# Power_Module_3_0.net
KiCad netlist of a schematic drawn in EAGLE
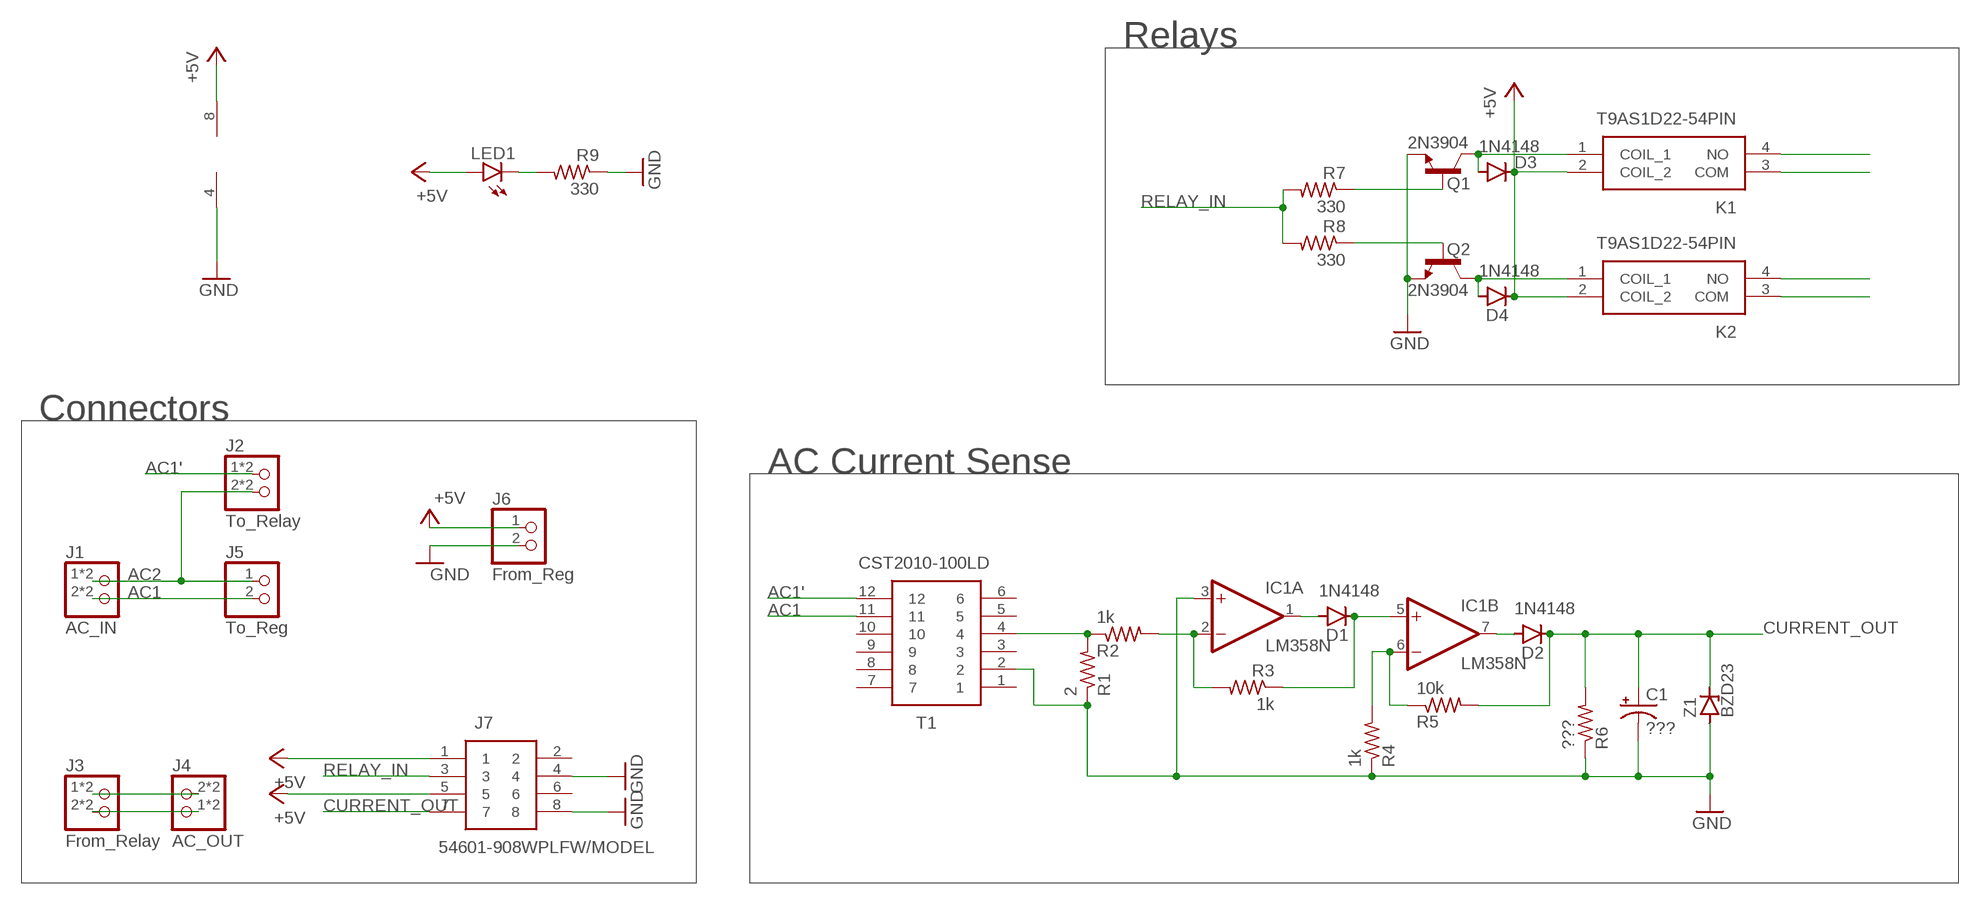
[diagram p0: schematic, sheet 1]

(export (version "E")
  (design (tool "Eeschema 10.0.6"))
  (components
    (comp (ref "C1")
      (value "???")
      (footprint "eagle-import:E1,8-4")
      (libsource (lib "eagle-import") (part "CPOL-USE1.8-4"))
    )
    (comp (ref "D1")
      (value "1N4148")
      (footprint "eagle-import:DO35-7")
      (libsource (lib "eagle-import") (part "1N4148DO35-7"))
    )
    (comp (ref "D2")
      (value "1N4148")
      (footprint "eagle-import:DO35-7")
      (libsource (lib "eagle-import") (part "1N4148DO35-7"))
    )
    (comp (ref "D3")
      (value "1N4148")
      (footprint "eagle-import:DO35-7")
      (libsource (lib "eagle-import") (part "1N4148DO35-7"))
    )
    (comp (ref "D4")
      (value "1N4148")
      (footprint "eagle-import:DO35-7")
      (libsource (lib "eagle-import") (part "1N4148DO35-7"))
    )
    (comp (ref "IC1")
      (value "LM358N")
      (footprint "eagle-import:DIL08")
      (libsource (lib "eagle-import") (part "LM358N"))
    )
    (comp (ref "J1")
      (value "AC_IN")
      (footprint "eagle-import:HDRRA4W64P762_2X2_1016X254X556B")
      (libsource (lib "eagle-import") (part "VC0200500000GVC0200500000G"))
    )
    (comp (ref "J2")
      (value "To_Relay")
      (footprint "eagle-import:HDRRA4W64P762_2X2_1016X254X556B")
      (libsource (lib "eagle-import") (part "VC0200500000GVC0200500000G"))
    )
    (comp (ref "J3")
      (value "From_Relay")
      (footprint "eagle-import:HDRRA4W64P762_2X2_1016X254X556B")
      (libsource (lib "eagle-import") (part "VC0200500000GVC0200500000G"))
    )
    (comp (ref "J4")
      (value "AC_OUT")
      (footprint "eagle-import:HDRRA4W64P762_2X2_1016X254X556B")
      (libsource (lib "eagle-import") (part "VC0200500000GVC0200500000G"))
    )
    (comp (ref "J5")
      (value "To_Reg")
      (footprint "eagle-import:HDRV2W64P792_1X2_1016X508X838B")
      (libsource (lib "eagle-import") (part "VH_1X2GAP"))
    )
    (comp (ref "J6")
      (value "From_Reg")
      (footprint "eagle-import:HDRV2W165P396_1X2_1016X508X838B")
      (libsource (lib "eagle-import") (part "VH_1X2"))
    )
    (comp (ref "J7")
      (value "54601-908WPLFW/MODEL")
      (footprint "eagle-import:HDRV4W64P254_1X4_1016X508X838B")
      (libsource (lib "eagle-import") (part "54601-908WPLFW/MODEL"))
    )
    (comp (ref "K1")
      (value "T9AS1D22-54PIN")
      (footprint "eagle-import:T9AS5D1212313932103-2")
      (libsource (lib "eagle-import") (part "T9AS1D22-54PIN"))
    )
    (comp (ref "K2")
      (value "T9AS1D22-54PIN")
      (footprint "eagle-import:T9AS5D1212313932103-2")
      (libsource (lib "eagle-import") (part "T9AS1D22-54PIN"))
    )
    (comp (ref "LED1")
      (value "LED5MM")
      (footprint "eagle-import:LED5MM")
      (libsource (lib "eagle-import") (part "LED5MM"))
    )
    (comp (ref "Q1")
      (value "2N3904")
      (footprint "eagle-import:TO92")
      (libsource (lib "eagle-import") (part "2N3904"))
    )
    (comp (ref "Q2")
      (value "2N3904")
      (footprint "eagle-import:TO92")
      (libsource (lib "eagle-import") (part "2N3904"))
    )
    (comp (ref "R1")
      (value "2")
      (footprint "eagle-import:0204_7")
      (libsource (lib "eagle-import") (part "R-US"))
    )
    (comp (ref "R2")
      (value "1k")
      (footprint "eagle-import:0204_7")
      (libsource (lib "eagle-import") (part "R-US"))
    )
    (comp (ref "R3")
      (value "1k")
      (footprint "eagle-import:0204_7")
      (libsource (lib "eagle-import") (part "R-US"))
    )
    (comp (ref "R4")
      (value "1k")
      (footprint "eagle-import:0204_7")
      (libsource (lib "eagle-import") (part "R-US"))
    )
    (comp (ref "R5")
      (value "10k")
      (footprint "eagle-import:0204_7")
      (libsource (lib "eagle-import") (part "R-US"))
    )
    (comp (ref "R6")
      (value "???")
      (footprint "eagle-import:0204_7")
      (libsource (lib "eagle-import") (part "R-US"))
    )
    (comp (ref "R7")
      (value "330")
      (footprint "eagle-import:0204_7")
      (libsource (lib "eagle-import") (part "R-US"))
    )
    (comp (ref "R8")
      (value "330")
      (footprint "eagle-import:0204_7")
      (libsource (lib "eagle-import") (part "R-US"))
    )
    (comp (ref "R9")
      (value "330")
      (footprint "eagle-import:0204_7")
      (libsource (lib "eagle-import") (part "R-US"))
    )
    (comp (ref "T1")
      (value "CST2010-100LD")
      (footprint "eagle-import:CST2010100LD")
      (fields (field (name "MOUSER_PART_NUMBER") "994-CST2010-100LD"))
      (libsource (lib "eagle-import") (part "CST2010-100LD"))
    )
    (comp (ref "Z1")
      (value "BZD23")
      (footprint "eagle-import:SOD81")
      (libsource (lib "eagle-import") (part "BZD23"))
    )
  )
  (nets
    (net (code "1") (name "+5V") (class "Default")
      (node (ref "D3") (pin "C") (pinfunction "C_C") (pintype "passive"))
      (node (ref "D4") (pin "C") (pinfunction "C_C") (pintype "passive"))
      (node (ref "IC1") (pin "8") (pinfunction "V+_8") (pintype "power_in"))
      (node (ref "J6") (pin "1") (pinfunction "1_1") (pintype "passive"))
      (node (ref "J7") (pin "1") (pinfunction "1_1") (pintype "bidirectional"))
      (node (ref "J7") (pin "5") (pinfunction "5_5") (pintype "bidirectional"))
      (node (ref "K1") (pin "2") (pinfunction "COIL_2_2") (pintype "bidirectional"))
      (node (ref "K2") (pin "2") (pinfunction "COIL_2_2") (pintype "bidirectional"))
      (node (ref "LED1") (pin "A") (pinfunction "A_A") (pintype "passive"))
    )
    (net (code "2") (name "/AC1") (class "Default")
      (node (ref "J1") (pin "2") (pinfunction "2_2") (pintype "passive"))
      (node (ref "J1") (pin "3") (pinfunction "2_3") (pintype "passive"))
      (node (ref "J5") (pin "2") (pinfunction "2_2") (pintype "passive"))
      (node (ref "T1") (pin "11") (pinfunction "11_11") (pintype "bidirectional"))
    )
    (net (code "3") (name "/AC1'") (class "Default")
      (node (ref "J2") (pin "1") (pinfunction "1_1") (pintype "passive"))
      (node (ref "J2") (pin "4") (pinfunction "1_4") (pintype "passive"))
      (node (ref "T1") (pin "12") (pinfunction "12_12") (pintype "bidirectional"))
    )
    (net (code "4") (name "/AC2") (class "Default")
      (node (ref "J1") (pin "1") (pinfunction "1_1") (pintype "passive"))
      (node (ref "J1") (pin "4") (pinfunction "1_4") (pintype "passive"))
      (node (ref "J2") (pin "2") (pinfunction "2_2") (pintype "passive"))
      (node (ref "J2") (pin "3") (pinfunction "2_3") (pintype "passive"))
      (node (ref "J5") (pin "1") (pinfunction "1_1") (pintype "passive"))
    )
    (net (code "5") (name "/CURRENT_OUT") (class "Default")
      (node (ref "C1") (pin "+") (pinfunction "+_+") (pintype "passive"))
      (node (ref "D2") (pin "C") (pinfunction "C_C") (pintype "passive"))
      (node (ref "J7") (pin "7") (pinfunction "7_7") (pintype "bidirectional"))
      (node (ref "R5") (pin "2") (pinfunction "2_2") (pintype "passive"))
      (node (ref "R6") (pin "2") (pinfunction "2_2") (pintype "passive"))
      (node (ref "Z1") (pin "C") (pinfunction "C_C") (pintype "passive"))
    )
    (net (code "6") (name "/RELAY_IN") (class "Default")
      (node (ref "J7") (pin "3") (pinfunction "3_3") (pintype "bidirectional"))
      (node (ref "R7") (pin "2") (pinfunction "2_2") (pintype "passive"))
      (node (ref "R8") (pin "2") (pinfunction "2_2") (pintype "passive"))
    )
    (net (code "7") (name "GND") (class "Default")
      (node (ref "C1") (pin "-") (pinfunction "-_-") (pintype "passive"))
      (node (ref "IC1") (pin "3") (pinfunction "+IN_3") (pintype "input"))
      (node (ref "IC1") (pin "4") (pinfunction "V-_4") (pintype "power_in"))
      (node (ref "J6") (pin "2") (pinfunction "2_2") (pintype "passive"))
      (node (ref "J7") (pin "4") (pinfunction "4_4") (pintype "bidirectional"))
      (node (ref "J7") (pin "8") (pinfunction "8_8") (pintype "bidirectional"))
      (node (ref "Q1") (pin "3") (pinfunction "E_3") (pintype "passive"))
      (node (ref "Q2") (pin "3") (pinfunction "E_3") (pintype "passive"))
      (node (ref "R1") (pin "1") (pinfunction "1_1") (pintype "passive"))
      (node (ref "R4") (pin "1") (pinfunction "1_1") (pintype "passive"))
      (node (ref "R6") (pin "1") (pinfunction "1_1") (pintype "passive"))
      (node (ref "R9") (pin "1") (pinfunction "1_1") (pintype "passive"))
      (node (ref "T1") (pin "2") (pinfunction "2_2") (pintype "bidirectional"))
      (node (ref "Z1") (pin "A") (pinfunction "A_A") (pintype "passive"))
    )
    (net (code "8") (name "Net-(IC1A--IN)") (class "Default")
      (node (ref "IC1") (pin "2") (pinfunction "-IN_2") (pintype "input"))
      (node (ref "R2") (pin "2") (pinfunction "2_2") (pintype "passive"))
      (node (ref "R3") (pin "2") (pinfunction "2_2") (pintype "passive"))
    )
    (net (code "9") (name "Net-(IC1A-OUT)") (class "Default")
      (node (ref "D1") (pin "A") (pinfunction "A_A") (pintype "passive"))
      (node (ref "IC1") (pin "1") (pinfunction "OUT_1") (pintype "output"))
    )
    (net (code "10") (name "Net-(IC1B-+IN)") (class "Default")
      (node (ref "D1") (pin "C") (pinfunction "C_C") (pintype "passive"))
      (node (ref "IC1") (pin "5") (pinfunction "+IN_5") (pintype "input"))
      (node (ref "R3") (pin "1") (pinfunction "1_1") (pintype "passive"))
    )
    (net (code "11") (name "Net-(IC1B--IN)") (class "Default")
      (node (ref "IC1") (pin "6") (pinfunction "-IN_6") (pintype "input"))
      (node (ref "R4") (pin "2") (pinfunction "2_2") (pintype "passive"))
      (node (ref "R5") (pin "1") (pinfunction "1_1") (pintype "passive"))
    )
    (net (code "12") (name "Net-(IC1B-OUT)") (class "Default")
      (node (ref "D2") (pin "A") (pinfunction "A_A") (pintype "passive"))
      (node (ref "IC1") (pin "7") (pinfunction "OUT_7") (pintype "output"))
    )
    (net (code "13") (name "Net-(J3-1-Pad4)") (class "Default")
      (node (ref "J3") (pin "1") (pinfunction "1_1") (pintype "passive"))
      (node (ref "J3") (pin "4") (pinfunction "1_4") (pintype "passive"))
      (node (ref "J4") (pin "2") (pinfunction "2_2") (pintype "passive"))
      (node (ref "J4") (pin "3") (pinfunction "2_3") (pintype "passive"))
    )
    (net (code "14") (name "Net-(J3-2-Pad3)") (class "Default")
      (node (ref "J3") (pin "2") (pinfunction "2_2") (pintype "passive"))
      (node (ref "J3") (pin "3") (pinfunction "2_3") (pintype "passive"))
      (node (ref "J4") (pin "1") (pinfunction "1_1") (pintype "passive"))
      (node (ref "J4") (pin "4") (pinfunction "1_4") (pintype "passive"))
    )
    (net (code "15") (name "Net-(K1-COIL_1)") (class "Default")
      (node (ref "D3") (pin "A") (pinfunction "A_A") (pintype "passive"))
      (node (ref "K1") (pin "1") (pinfunction "COIL_1_1") (pintype "bidirectional"))
      (node (ref "Q1") (pin "1") (pinfunction "C_1") (pintype "passive"))
    )
    (net (code "16") (name "Net-(K2-COIL_1)") (class "Default")
      (node (ref "D4") (pin "A") (pinfunction "A_A") (pintype "passive"))
      (node (ref "K2") (pin "1") (pinfunction "COIL_1_1") (pintype "bidirectional"))
      (node (ref "Q2") (pin "1") (pinfunction "C_1") (pintype "passive"))
    )
    (net (code "17") (name "Net-(LED1-C)") (class "Default")
      (node (ref "LED1") (pin "K") (pinfunction "C_K") (pintype "passive"))
      (node (ref "R9") (pin "2") (pinfunction "2_2") (pintype "passive"))
    )
    (net (code "18") (name "Net-(Q1-B)") (class "Default")
      (node (ref "Q1") (pin "2") (pinfunction "B_2") (pintype "passive"))
      (node (ref "R7") (pin "1") (pinfunction "1_1") (pintype "passive"))
    )
    (net (code "19") (name "Net-(Q2-B)") (class "Default")
      (node (ref "Q2") (pin "2") (pinfunction "B_2") (pintype "passive"))
      (node (ref "R8") (pin "1") (pinfunction "1_1") (pintype "passive"))
    )
    (net (code "20") (name "Net-(R1-Pad2)") (class "Default")
      (node (ref "R1") (pin "2") (pinfunction "2_2") (pintype "passive"))
      (node (ref "R2") (pin "1") (pinfunction "1_1") (pintype "passive"))
      (node (ref "T1") (pin "4") (pinfunction "4_4") (pintype "bidirectional"))
    )
    (net (code "21") (name "unconnected-(J7-Pad2)") (class "Default")
      (node (ref "J7") (pin "2") (pinfunction "2_2") (pintype "bidirectional"))
    )
    (net (code "22") (name "unconnected-(J7-Pad6)") (class "Default")
      (node (ref "J7") (pin "6") (pinfunction "6_6") (pintype "bidirectional"))
    )
    (net (code "23") (name "unconnected-(K1-COM-Pad3)") (class "Default")
      (node (ref "K1") (pin "3") (pinfunction "COM_3") (pintype "bidirectional"))
    )
    (net (code "24") (name "unconnected-(K1-NO-Pad4)") (class "Default")
      (node (ref "K1") (pin "4") (pinfunction "NO_4") (pintype "bidirectional"))
    )
    (net (code "25") (name "unconnected-(K2-COM-Pad3)") (class "Default")
      (node (ref "K2") (pin "3") (pinfunction "COM_3") (pintype "bidirectional"))
    )
    (net (code "26") (name "unconnected-(K2-NO-Pad4)") (class "Default")
      (node (ref "K2") (pin "4") (pinfunction "NO_4") (pintype "bidirectional"))
    )
    (net (code "27") (name "unconnected-(T1-Pad1)") (class "Default")
      (node (ref "T1") (pin "1") (pinfunction "1_1") (pintype "bidirectional"))
    )
    (net (code "28") (name "unconnected-(T1-Pad3)") (class "Default")
      (node (ref "T1") (pin "3") (pinfunction "3_3") (pintype "bidirectional"))
    )
    (net (code "29") (name "unconnected-(T1-Pad5)") (class "Default")
      (node (ref "T1") (pin "5") (pinfunction "5_5") (pintype "bidirectional"))
    )
    (net (code "30") (name "unconnected-(T1-Pad6)") (class "Default")
      (node (ref "T1") (pin "6") (pinfunction "6_6") (pintype "bidirectional"))
    )
    (net (code "31") (name "unconnected-(T1-Pad7)") (class "Default")
      (node (ref "T1") (pin "7") (pinfunction "7_7") (pintype "bidirectional"))
    )
    (net (code "32") (name "unconnected-(T1-Pad8)") (class "Default")
      (node (ref "T1") (pin "8") (pinfunction "8_8") (pintype "bidirectional"))
    )
    (net (code "33") (name "unconnected-(T1-Pad9)") (class "Default")
      (node (ref "T1") (pin "9") (pinfunction "9_9") (pintype "bidirectional"))
    )
    (net (code "34") (name "unconnected-(T1-Pad10)") (class "Default")
      (node (ref "T1") (pin "10") (pinfunction "10_10") (pintype "bidirectional"))
    )
  )
)
